# RAM.net
KiCad netlist of a schematic drawn in Altium Designer
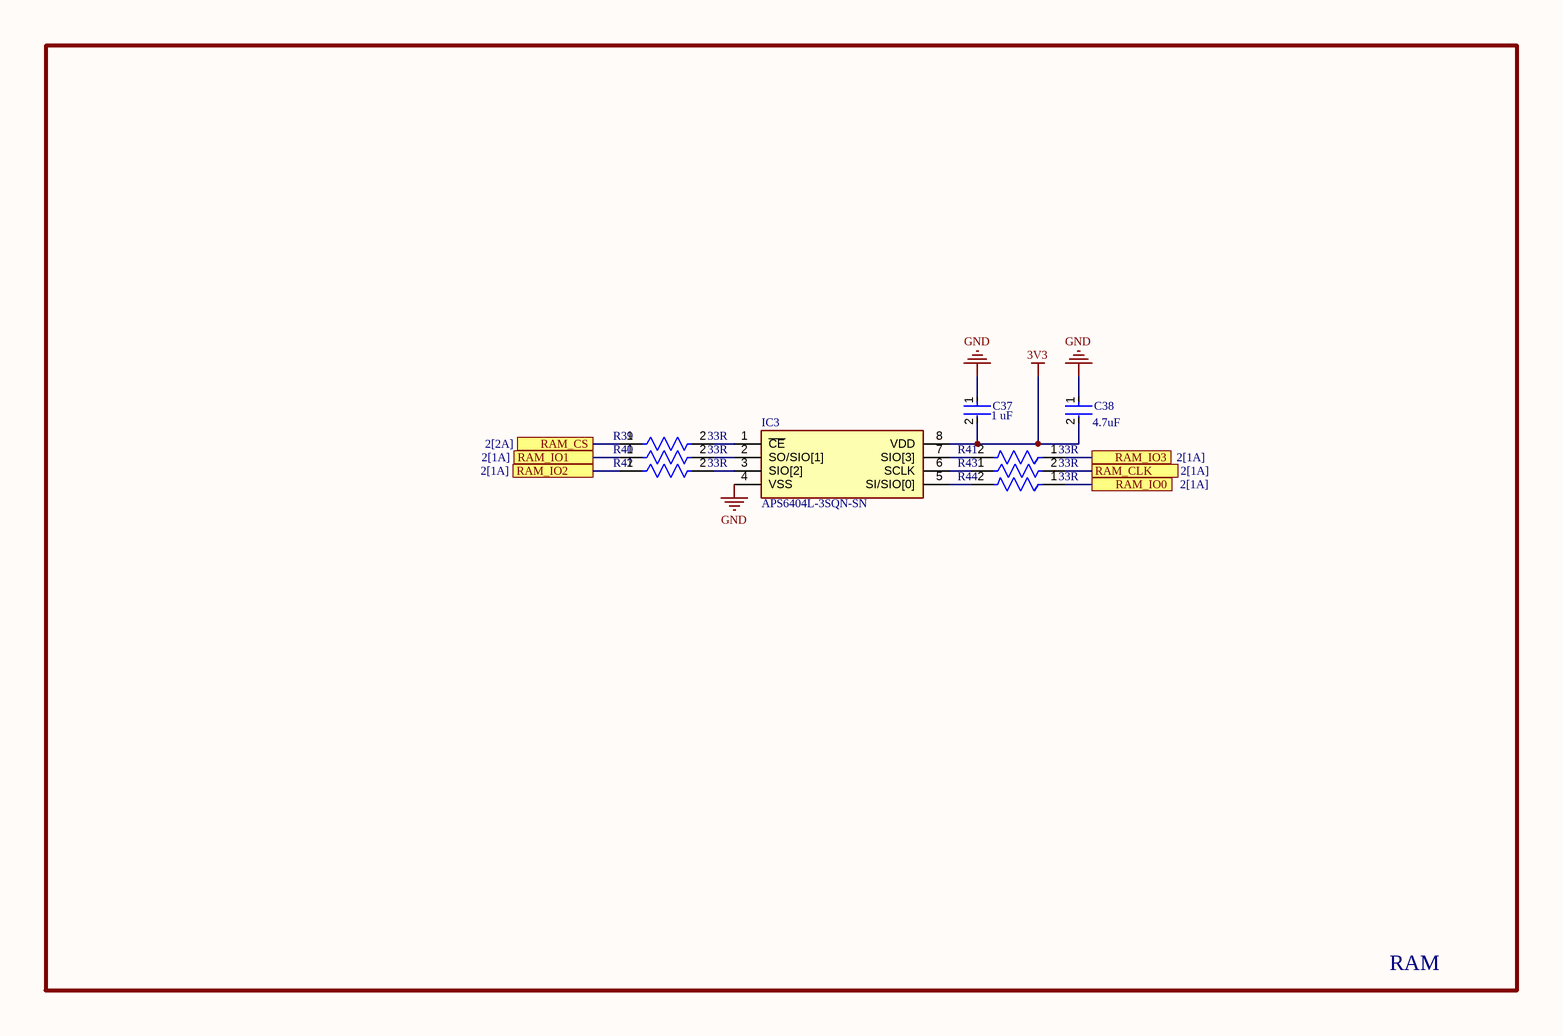
[diagram p0: RAM.SchDoc]

(export (version "E")
  (design (tool "Eeschema 10.0.6"))
  (components
    (comp (ref "C37")
      (value "CC0805KKX5R6BB105")
      (footprint "FP-CC0805-0_85-MFG")
      (description "CAP CER 1UF 10V X5R 0805")
      (fields
        (field (name "TOLERANCE") "0.1")
        (field (name "OCTOPART") "https://octopart.com/cc0805kkx5r6bb105-yageo-9292777")
        (field (name "CAPACITANCE") "1 uF")
      )
      (libsource (lib "Altium Content Vault") (part "11868f565c42a9108669ba33697ecf6"))
    )
    (comp (ref "C38")
      (value "C2012X7R1A475K125AC")
      (footprint "FP-C2012-125-0_2-IPC_B")
      (description "Multilayer Ceramic Capacitors 4.7μF ±10% 10V X7R SMD 0805")
      (fields (field (name "TOLERANCE") "10%") (field (name "CAPACITANCE") "4.7uF"))
      (libsource (lib "Altium Content Vault") (part "b4654b650e69147ec39a6b967a45e02"))
    )
    (comp (ref "IC3")
      (value "APS6404L-3SQN-SN")
      (footprint "SamacSys:SOIC127P600X175-8N")
      (description "Integrated Circuit")
      (libsource (lib "*") (part "APS6404L-3SQN-SN"))
    )
    (comp (ref "R39")
      (value "RMCF0805FT33R0")
      (footprint "FP-RMCF0805-MFG")
      (description "33Ω ±1% 0.125W 0805 Thick Film Chip Resistor AEC-Q200 compliant")
      (fields (field (name "RESISTANCE") "33R") (field (name "TOLERANCE") "1%"))
      (libsource (lib "Altium Content Vault") (part "1029c3af85768c4190bb7ad29bc67b5"))
    )
    (comp (ref "R40")
      (value "RMCF0805FT33R0")
      (footprint "FP-RMCF0805-MFG")
      (description "33Ω ±1% 0.125W 0805 Thick Film Chip Resistor AEC-Q200 compliant")
      (fields (field (name "RESISTANCE") "33R") (field (name "TOLERANCE") "1%"))
      (libsource (lib "Altium Content Vault") (part "1029c3af85768c4190bb7ad29bc67b5"))
    )
    (comp (ref "R41")
      (value "RMCF0805FT33R0")
      (footprint "FP-RMCF0805-MFG")
      (description "33Ω ±1% 0.125W 0805 Thick Film Chip Resistor AEC-Q200 compliant")
      (fields (field (name "RESISTANCE") "33R") (field (name "TOLERANCE") "1%"))
      (libsource (lib "Altium Content Vault") (part "1029c3af85768c4190bb7ad29bc67b5"))
    )
    (comp (ref "R42")
      (value "RMCF0805FT33R0")
      (footprint "FP-RMCF0805-MFG")
      (description "33Ω ±1% 0.125W 0805 Thick Film Chip Resistor AEC-Q200 compliant")
      (fields (field (name "RESISTANCE") "33R") (field (name "TOLERANCE") "1%"))
      (libsource (lib "Altium Content Vault") (part "1029c3af85768c4190bb7ad29bc67b5"))
    )
    (comp (ref "R43")
      (value "RMCF0805FT33R0")
      (footprint "FP-RMCF0805-MFG")
      (description "33Ω ±1% 0.125W 0805 Thick Film Chip Resistor AEC-Q200 compliant")
      (fields (field (name "RESISTANCE") "33R") (field (name "TOLERANCE") "1%"))
      (libsource (lib "Altium Content Vault") (part "1029c3af85768c4190bb7ad29bc67b5"))
    )
    (comp (ref "R44")
      (value "RMCF0805FT33R0")
      (footprint "FP-RMCF0805-MFG")
      (description "33Ω ±1% 0.125W 0805 Thick Film Chip Resistor AEC-Q200 compliant")
      (fields (field (name "RESISTANCE") "33R") (field (name "TOLERANCE") "1%"))
      (libsource (lib "Altium Content Vault") (part "1029c3af85768c4190bb7ad29bc67b5"))
    )
  )
  (nets
    (net (code "1") (name "/RAM_CLK") (class "Default")
      (node (ref "R43") (pin "2") (pinfunction "2_2") (pintype "passive"))
    )
    (net (code "2") (name "/RAM_CS") (class "Default")
      (node (ref "R39") (pin "1") (pinfunction "1_1") (pintype "passive"))
    )
    (net (code "3") (name "/RAM_IO0") (class "Default")
      (node (ref "R44") (pin "1") (pinfunction "1_1") (pintype "passive"))
    )
    (net (code "4") (name "/RAM_IO1") (class "Default")
      (node (ref "R40") (pin "1") (pinfunction "1_1") (pintype "passive"))
    )
    (net (code "5") (name "/RAM_IO2") (class "Default")
      (node (ref "R42") (pin "1") (pinfunction "1_1") (pintype "passive"))
    )
    (net (code "6") (name "/RAM_IO3") (class "Default")
      (node (ref "R41") (pin "1") (pinfunction "1_1") (pintype "passive"))
    )
    (net (code "7") (name "3V3") (class "Default")
      (node (ref "C37") (pin "2") (pinfunction "2_2") (pintype "passive"))
      (node (ref "C38") (pin "2") (pinfunction "2_2") (pintype "passive"))
      (node (ref "IC3") (pin "8") (pinfunction "VDD_8") (pintype "passive"))
    )
    (net (code "8") (name "GND") (class "Default")
      (node (ref "C37") (pin "1") (pinfunction "1_1") (pintype "passive"))
      (node (ref "C38") (pin "1") (pinfunction "1_1") (pintype "passive"))
      (node (ref "IC3") (pin "4") (pinfunction "VSS_4") (pintype "passive"))
    )
    (net (code "9") (name "Net-(IC3-SCLK)") (class "Default")
      (node (ref "IC3") (pin "6") (pinfunction "SCLK_6") (pintype "passive"))
      (node (ref "R43") (pin "1") (pinfunction "1_1") (pintype "passive"))
    )
    (net (code "10") (name "Net-(IC3-SIO[2])") (class "Default")
      (node (ref "IC3") (pin "3") (pinfunction "SIO[2]_3") (pintype "passive"))
      (node (ref "R42") (pin "2") (pinfunction "2_2") (pintype "passive"))
    )
    (net (code "11") (name "Net-(IC3-SIO[3])") (class "Default")
      (node (ref "IC3") (pin "7") (pinfunction "SIO[3]_7") (pintype "passive"))
      (node (ref "R41") (pin "2") (pinfunction "2_2") (pintype "passive"))
    )
    (net (code "12") (name "Net-(IC3-SI{slash}SIO[0])") (class "Default")
      (node (ref "IC3") (pin "5") (pinfunction "SI/SIO[0]_5") (pintype "passive"))
      (node (ref "R44") (pin "2") (pinfunction "2_2") (pintype "passive"))
    )
    (net (code "13") (name "Net-(IC3-SO{slash}SIO[1])") (class "Default")
      (node (ref "IC3") (pin "2") (pinfunction "SO/SIO[1]_2") (pintype "passive"))
      (node (ref "R40") (pin "2") (pinfunction "2_2") (pintype "passive"))
    )
    (net (code "14") (name "Net-(IC3-~{CE})") (class "Default")
      (node (ref "IC3") (pin "1") (pinfunction "~{CE}_1") (pintype "passive"))
      (node (ref "R39") (pin "2") (pinfunction "2_2") (pintype "passive"))
    )
  )
)
